# BlocoMotor.net
KiCad netlist of a schematic drawn in Altium Designer
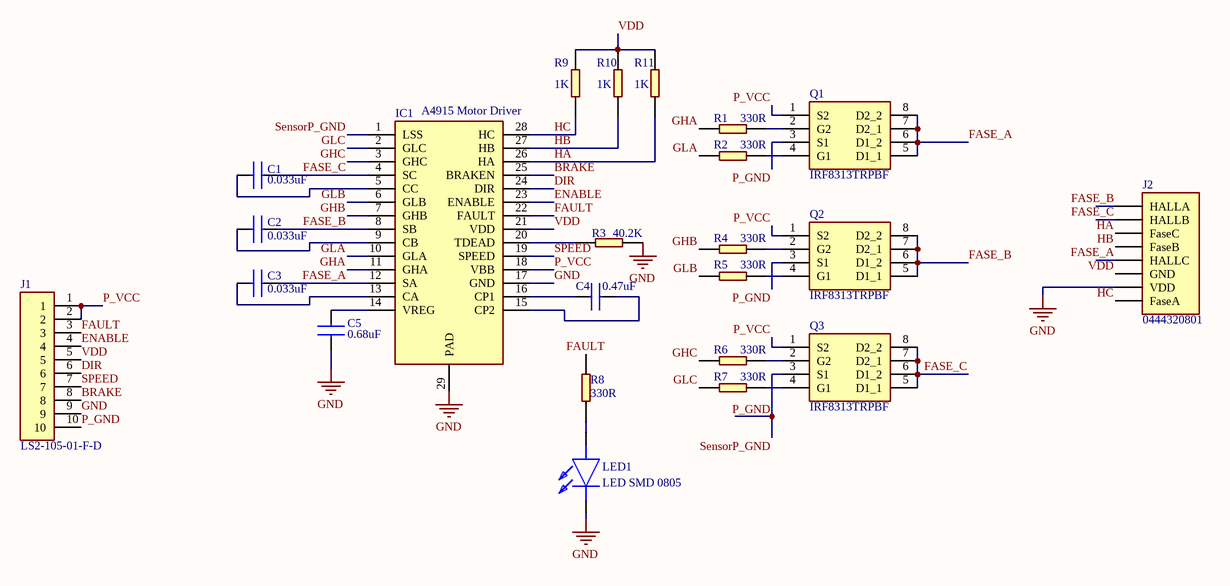
[diagram p0: BlocoMotor.SchDoc]

(export (version "E")
  (design (tool "Eeschema 10.0.6"))
  (components
    (comp (ref "C1")
      (value "0.033uF")
      (footprint "LIB_PCB_Kick:CAP0805 50v")
      (description "Capacitor\r\n08055A101JAT2A")
      (fields
        (field (name "MANUFACTURER_PART_NUMBER") "08055A101JAT2A")
        (field (name "MOUSER PART NUMBER") "581-08055A101J")
      )
      (libsource (lib "LIB_SCH_Main") (part "CAP 0805 50V"))
    )
    (comp (ref "C2")
      (value "0.033uF")
      (footprint "LIB_PCB_Kick:CAP0805 50v")
      (description "Capacitor\r\n08055A101JAT2A")
      (fields
        (field (name "MANUFACTURER_PART_NUMBER") "08055A101JAT2A")
        (field (name "MOUSER PART NUMBER") "581-08055A101J")
      )
      (libsource (lib "LIB_SCH_Main") (part "CAP 0805 50V"))
    )
    (comp (ref "C3")
      (value "0.033uF")
      (footprint "LIB_PCB_Kick:CAP0805 50v")
      (description "Capacitor\r\n08055A101JAT2A")
      (fields
        (field (name "MANUFACTURER_PART_NUMBER") "08055A101JAT2A")
        (field (name "MOUSER PART NUMBER") "581-08055A101J")
      )
      (libsource (lib "LIB_SCH_Main") (part "CAP 0805 50V"))
    )
    (comp (ref "C4")
      (value "0.47uF")
      (footprint "LIB_PCB_Kick:CAP0805 50v")
      (description "Capacitor\r\n08055A101JAT2A")
      (fields
        (field (name "MANUFACTURER_PART_NUMBER") "08055A101JAT2A")
        (field (name "MOUSER PART NUMBER") "581-08055A101J")
      )
      (libsource (lib "LIB_SCH_Main") (part "CAP 0805 50V"))
    )
    (comp (ref "C5")
      (value "0.68uF")
      (footprint "LIB_PCB_Kick:CAP0805 50v")
      (description "Capacitor\r\n08055A101JAT2A")
      (fields
        (field (name "MANUFACTURER_PART_NUMBER") "08055A101JAT2A")
        (field (name "MOUSER PART NUMBER") "581-08055A101J")
      )
      (libsource (lib "LIB_SCH_Main") (part "CAP 0805 50V"))
    )
    (comp (ref "IC1")
      (value "A4915 Motor Driver")
      (footprint "LIB_PCB_MAIN:A4915 Motor Driver")
      (fields (field (name "MANUFACTURER_PART_NUMBER") "A4915MLPTR-T"))
      (libsource (lib "LIB_SCH_MAIN") (part "A4915 Motor Driver"))
    )
    (comp (ref "J1")
      (value "LS2-105-01-F-D")
      (footprint "LIB_PCB_MAIN:CONN SINAL 10POS")
      (description "CONN SELF-MATE 10POS VERT GOLD\r\n\r\nSAM11451-ND\r\n\r\nLS2-105-01-F-D")
      (fields
        (field (name "MANUFACTURER_PART_NUMBER") "10132797-015100LF")
        (field (name "MOUSER PART NUMBER") "649-10132797015100LF")
      )
      (libsource (lib "LIB_SCH_MAIN") (part "CONN SInal Motor"))
    )
    (comp (ref "J2")
      (value "0444320801")
      (footprint "LIB_PCB_MAIN:CONN Main Motor")
      (fields (field (name "MANUFACTURER_PART_NUMBER") "0444320802"))
      (libsource (lib "LIB_SCH_Main") (part "CONN Main Motor"))
    )
    (comp (ref "LED1")
      (value "LED SMD 0805")
      (footprint "LIB_PCB_MAIN:LED SMD")
      (fields
        (field (name "MANUFACTURER_PART_NUMBER") "LTST-C170KRKT")
        (field (name "MOUSER PART NUMBER") "859-LTST-C170KRKT")
        (field (name "RS PART NUMBER") "6920916P")
      )
      (libsource (lib "LIB_SCH_MAIN") (part "LED SMD 0805"))
    )
    (comp (ref "Q1")
      (value "IRF8313TRPBF")
      (footprint "LIB_PCB_MAIN:MOSFET MOTOR 2N-CH 30V 9.7A 8-SOIC")
      (description "Mosfet Array 2 N-Channel (Dual) 30V 9.7A 2W Surface Mount 8-SO\r\n\r\nIRF8313TRPBFTR-ND")
      (fields
        (field (name "MOUSER PART NUMBER") "942-IRF8313TRPBF")
        (field (name "RS PART NUMBER") "8273903")
      )
      (libsource (lib "LIB_SCH_MAIN") (part "MOSFET MOTOR 2N-CH 30V 9.7A 8-SOIC"))
    )
    (comp (ref "Q2")
      (value "IRF8313TRPBF")
      (footprint "LIB_PCB_MAIN:MOSFET MOTOR 2N-CH 30V 9.7A 8-SOIC")
      (description "Mosfet Array 2 N-Channel (Dual) 30V 9.7A 2W Surface Mount 8-SO\r\n\r\nIRF8313TRPBFTR-ND")
      (fields
        (field (name "MOUSER PART NUMBER") "942-IRF8313TRPBF")
        (field (name "RS PART NUMBER") "8273903")
      )
      (libsource (lib "LIB_SCH_MAIN") (part "MOSFET MOTOR 2N-CH 30V 9.7A 8-SOIC"))
    )
    (comp (ref "Q3")
      (value "IRF8313TRPBF")
      (footprint "LIB_PCB_MAIN:MOSFET MOTOR 2N-CH 30V 9.7A 8-SOIC")
      (description "Mosfet Array 2 N-Channel (Dual) 30V 9.7A 2W Surface Mount 8-SO\r\n\r\nIRF8313TRPBFTR-ND")
      (fields
        (field (name "MOUSER PART NUMBER") "942-IRF8313TRPBF")
        (field (name "RS PART NUMBER") "8273903")
      )
      (libsource (lib "LIB_SCH_MAIN") (part "MOSFET MOTOR 2N-CH 30V 9.7A 8-SOIC"))
    )
    (comp (ref "R1")
      (value "330R")
      (footprint "LIB_PCB_Kick:RES 0805")
      (description "Resistor")
      (fields
        (field (name "MANUFACTURER_PART_NUMBER") "CPF0805B105RE1")
        (field (name "MOUSER PART NUMBER") "279-CPF0805B105RE1")
      )
      (libsource (lib "") (part "Resistor 0805_1"))
    )
    (comp (ref "R2")
      (value "330R")
      (footprint "LIB_PCB_Kick:RES 0805")
      (description "Resistor")
      (fields
        (field (name "MANUFACTURER_PART_NUMBER") "CPF0805B105RE1")
        (field (name "MOUSER PART NUMBER") "279-CPF0805B105RE1")
      )
      (libsource (lib "") (part "Resistor 0805_1"))
    )
    (comp (ref "R3")
      (value "40.2K")
      (footprint "LIB_PCB_Kick:RES 0805")
      (description "Resistor")
      (fields
        (field (name "MANUFACTURER_PART_NUMBER") "CPF0805B105RE1")
        (field (name "MOUSER PART NUMBER") "279-CPF0805B105RE1")
      )
      (libsource (lib "") (part "Resistor 0805_1"))
    )
    (comp (ref "R4")
      (value "330R")
      (footprint "LIB_PCB_Kick:RES 0805")
      (description "Resistor")
      (fields
        (field (name "MANUFACTURER_PART_NUMBER") "CPF0805B105RE1")
        (field (name "MOUSER PART NUMBER") "279-CPF0805B105RE1")
      )
      (libsource (lib "") (part "Resistor 0805_1"))
    )
    (comp (ref "R5")
      (value "330R")
      (footprint "LIB_PCB_Kick:RES 0805")
      (description "Resistor")
      (fields
        (field (name "MANUFACTURER_PART_NUMBER") "CPF0805B105RE1")
        (field (name "MOUSER PART NUMBER") "279-CPF0805B105RE1")
      )
      (libsource (lib "") (part "Resistor 0805_1"))
    )
    (comp (ref "R6")
      (value "330R")
      (footprint "LIB_PCB_Kick:RES 0805")
      (description "Resistor")
      (fields
        (field (name "MANUFACTURER_PART_NUMBER") "CPF0805B105RE1")
        (field (name "MOUSER PART NUMBER") "279-CPF0805B105RE1")
      )
      (libsource (lib "") (part "Resistor 0805_1"))
    )
    (comp (ref "R7")
      (value "330R")
      (footprint "LIB_PCB_Kick:RES 0805")
      (description "Resistor")
      (fields
        (field (name "MANUFACTURER_PART_NUMBER") "CPF0805B105RE1")
        (field (name "MOUSER PART NUMBER") "279-CPF0805B105RE1")
      )
      (libsource (lib "") (part "Resistor 0805_1"))
    )
    (comp (ref "R8")
      (value "330R")
      (footprint "LIB_PCB_Kick:RES 0805")
      (description "Resistor")
      (fields
        (field (name "MANUFACTURER_PART_NUMBER") "CPF0805B105RE1")
        (field (name "MOUSER PART NUMBER") "279-CPF0805B105RE1")
      )
      (libsource (lib "LIB_SCH_Main") (part "Resistor 0805"))
    )
    (comp (ref "R9")
      (value "1K")
      (footprint "LIB_PCB_Kick:RES 0805")
      (description "Resistor")
      (fields
        (field (name "MANUFACTURER_PART_NUMBER") "CPF0805B105RE1")
        (field (name "MOUSER PART NUMBER") "279-CPF0805B105RE1")
      )
      (libsource (lib "LIB_SCH_Main") (part "Resistor 0805"))
    )
    (comp (ref "R10")
      (value "1K")
      (footprint "LIB_PCB_Kick:RES 0805")
      (description "Resistor")
      (fields
        (field (name "MANUFACTURER_PART_NUMBER") "CPF0805B105RE1")
        (field (name "MOUSER PART NUMBER") "279-CPF0805B105RE1")
      )
      (libsource (lib "LIB_SCH_Main") (part "Resistor 0805"))
    )
    (comp (ref "R11")
      (value "1K")
      (footprint "LIB_PCB_Kick:RES 0805")
      (description "Resistor")
      (fields
        (field (name "MANUFACTURER_PART_NUMBER") "CPF0805B105RE1")
        (field (name "MOUSER PART NUMBER") "279-CPF0805B105RE1")
      )
      (libsource (lib "LIB_SCH_Main") (part "Resistor 0805"))
    )
  )
  (nets
    (net (code "1") (name "/BRAKE") (class "Default")
      (node (ref "IC1") (pin "25") (pinfunction "BRAKEN_25") (pintype "passive"))
      (node (ref "J1") (pin "8") (pinfunction "8_8") (pintype "passive"))
    )
    (net (code "2") (name "/DIR") (class "Default")
      (node (ref "IC1") (pin "24") (pinfunction "DIR_24") (pintype "passive"))
      (node (ref "J1") (pin "6") (pinfunction "6_6") (pintype "passive"))
    )
    (net (code "3") (name "/ENABLE") (class "Default")
      (node (ref "IC1") (pin "23") (pinfunction "ENABLE_23") (pintype "passive"))
      (node (ref "J1") (pin "4") (pinfunction "4_4") (pintype "passive"))
    )
    (net (code "4") (name "/FASE_A") (class "Default")
      (node (ref "C3") (pin "1") (pinfunction "1_1") (pintype "passive"))
      (node (ref "IC1") (pin "12") (pinfunction "SA_12") (pintype "passive"))
      (node (ref "J2") (pin "5") (pinfunction "HALLC_5") (pintype "passive"))
      (node (ref "Q1") (pin "5") (pinfunction "D1_1_5") (pintype "passive"))
      (node (ref "Q1") (pin "6") (pinfunction "D1_2_6") (pintype "passive"))
      (node (ref "Q1") (pin "7") (pinfunction "D2_1_7") (pintype "passive"))
      (node (ref "Q1") (pin "8") (pinfunction "D2_2_8") (pintype "passive"))
    )
    (net (code "5") (name "/FASE_B") (class "Default")
      (node (ref "C2") (pin "1") (pinfunction "1_1") (pintype "passive"))
      (node (ref "IC1") (pin "8") (pinfunction "SB_8") (pintype "passive"))
      (node (ref "J2") (pin "1") (pinfunction "HALLA_1") (pintype "passive"))
      (node (ref "Q2") (pin "5") (pinfunction "D1_1_5") (pintype "passive"))
      (node (ref "Q2") (pin "6") (pinfunction "D1_2_6") (pintype "passive"))
      (node (ref "Q2") (pin "7") (pinfunction "D2_1_7") (pintype "passive"))
      (node (ref "Q2") (pin "8") (pinfunction "D2_2_8") (pintype "passive"))
    )
    (net (code "6") (name "/FASE_C") (class "Default")
      (node (ref "C1") (pin "1") (pinfunction "1_1") (pintype "passive"))
      (node (ref "IC1") (pin "4") (pinfunction "SC_4") (pintype "passive"))
      (node (ref "J2") (pin "2") (pinfunction "HALLB_2") (pintype "passive"))
      (node (ref "Q3") (pin "5") (pinfunction "D1_1_5") (pintype "passive"))
      (node (ref "Q3") (pin "6") (pinfunction "D1_2_6") (pintype "passive"))
      (node (ref "Q3") (pin "7") (pinfunction "D2_1_7") (pintype "passive"))
      (node (ref "Q3") (pin "8") (pinfunction "D2_2_8") (pintype "passive"))
    )
    (net (code "7") (name "/FAULT") (class "Default")
      (node (ref "IC1") (pin "22") (pinfunction "FAULT_22") (pintype "passive"))
      (node (ref "J1") (pin "3") (pinfunction "3_3") (pintype "passive"))
      (node (ref "R8") (pin "1") (pinfunction "1_1") (pintype "passive"))
    )
    (net (code "8") (name "/GHA") (class "Default")
      (node (ref "IC1") (pin "11") (pinfunction "GHA_11") (pintype "passive"))
      (node (ref "R1") (pin "1") (pinfunction "1_1") (pintype "passive"))
    )
    (net (code "9") (name "/GHB") (class "Default")
      (node (ref "IC1") (pin "7") (pinfunction "GHB_7") (pintype "passive"))
      (node (ref "R4") (pin "1") (pinfunction "1_1") (pintype "passive"))
    )
    (net (code "10") (name "/GHC") (class "Default")
      (node (ref "IC1") (pin "3") (pinfunction "GHC_3") (pintype "passive"))
      (node (ref "R6") (pin "1") (pinfunction "1_1") (pintype "passive"))
    )
    (net (code "11") (name "/GLA") (class "Default")
      (node (ref "IC1") (pin "10") (pinfunction "GLA_10") (pintype "passive"))
      (node (ref "R2") (pin "1") (pinfunction "1_1") (pintype "passive"))
    )
    (net (code "12") (name "/GLB") (class "Default")
      (node (ref "IC1") (pin "6") (pinfunction "GLB_6") (pintype "passive"))
      (node (ref "R5") (pin "1") (pinfunction "1_1") (pintype "passive"))
    )
    (net (code "13") (name "/GLC") (class "Default")
      (node (ref "IC1") (pin "2") (pinfunction "GLC_2") (pintype "passive"))
      (node (ref "R7") (pin "1") (pinfunction "1_1") (pintype "passive"))
    )
    (net (code "14") (name "/HA") (class "Default")
      (node (ref "IC1") (pin "26") (pinfunction "HA_26") (pintype "passive"))
      (node (ref "J2") (pin "3") (pinfunction "FaseC_3") (pintype "passive"))
      (node (ref "R11") (pin "2") (pinfunction "2_2") (pintype "passive"))
    )
    (net (code "15") (name "/HB") (class "Default")
      (node (ref "IC1") (pin "27") (pinfunction "HB_27") (pintype "passive"))
      (node (ref "J2") (pin "4") (pinfunction "FaseB_4") (pintype "passive"))
      (node (ref "R10") (pin "2") (pinfunction "2_2") (pintype "passive"))
    )
    (net (code "16") (name "/HC") (class "Default")
      (node (ref "IC1") (pin "28") (pinfunction "HC_28") (pintype "passive"))
      (node (ref "J2") (pin "8") (pinfunction "FaseA_8") (pintype "passive"))
      (node (ref "R9") (pin "2") (pinfunction "2_2") (pintype "passive"))
    )
    (net (code "17") (name "/P_GND") (class "Default")
      (node (ref "IC1") (pin "1") (pinfunction "LSS_1") (pintype "passive"))
      (node (ref "J1") (pin "10") (pinfunction "10_10") (pintype "passive"))
      (node (ref "Q1") (pin "3") (pinfunction "S1_3") (pintype "passive"))
      (node (ref "Q2") (pin "3") (pinfunction "S1_3") (pintype "passive"))
      (node (ref "Q3") (pin "3") (pinfunction "S1_3") (pintype "passive"))
    )
    (net (code "18") (name "/P_VCC") (class "Default")
      (node (ref "IC1") (pin "18") (pinfunction "VBB_18") (pintype "passive"))
      (node (ref "J1") (pin "1") (pinfunction "1_1") (pintype "passive"))
      (node (ref "J1") (pin "2") (pinfunction "2_2") (pintype "passive"))
      (node (ref "Q1") (pin "1") (pinfunction "S2_1") (pintype "passive"))
      (node (ref "Q2") (pin "1") (pinfunction "S2_1") (pintype "passive"))
      (node (ref "Q3") (pin "1") (pinfunction "S2_1") (pintype "passive"))
    )
    (net (code "19") (name "/SPEED") (class "Default")
      (node (ref "IC1") (pin "19") (pinfunction "SPEED_19") (pintype "passive"))
      (node (ref "J1") (pin "7") (pinfunction "7_7") (pintype "passive"))
    )
    (net (code "20") (name "/VDD") (class "Default")
      (node (ref "IC1") (pin "21") (pinfunction "VDD_21") (pintype "passive"))
      (node (ref "J1") (pin "5") (pinfunction "5_5") (pintype "passive"))
      (node (ref "J2") (pin "6") (pinfunction "GND_6") (pintype "passive"))
      (node (ref "R10") (pin "1") (pinfunction "1_1") (pintype "passive"))
      (node (ref "R11") (pin "1") (pinfunction "1_1") (pintype "passive"))
      (node (ref "R9") (pin "1") (pinfunction "1_1") (pintype "passive"))
    )
    (net (code "21") (name "GND") (class "Default")
      (node (ref "C5") (pin "1") (pinfunction "1_1") (pintype "passive"))
      (node (ref "IC1") (pin "17") (pinfunction "GND_17") (pintype "passive"))
      (node (ref "IC1") (pin "29") (pinfunction "PAD_29") (pintype "passive"))
      (node (ref "J1") (pin "9") (pinfunction "9_9") (pintype "passive"))
      (node (ref "J2") (pin "7") (pinfunction "VDD_7") (pintype "passive"))
      (node (ref "LED1") (pin "1") (pinfunction "K_1") (pintype "passive"))
      (node (ref "R3") (pin "2") (pinfunction "2_2") (pintype "passive"))
    )
    (net (code "22") (name "Net-(IC1-CA)") (class "Default")
      (node (ref "C3") (pin "2") (pinfunction "2_2") (pintype "passive"))
      (node (ref "IC1") (pin "13") (pinfunction "CA_13") (pintype "passive"))
    )
    (net (code "23") (name "Net-(IC1-CB)") (class "Default")
      (node (ref "C2") (pin "2") (pinfunction "2_2") (pintype "passive"))
      (node (ref "IC1") (pin "9") (pinfunction "CB_9") (pintype "passive"))
    )
    (net (code "24") (name "Net-(IC1-CC)") (class "Default")
      (node (ref "C1") (pin "2") (pinfunction "2_2") (pintype "passive"))
      (node (ref "IC1") (pin "5") (pinfunction "CC_5") (pintype "passive"))
    )
    (net (code "25") (name "Net-(IC1-CP1)") (class "Default")
      (node (ref "C4") (pin "2") (pinfunction "2_2") (pintype "passive"))
      (node (ref "IC1") (pin "16") (pinfunction "CP1_16") (pintype "passive"))
    )
    (net (code "26") (name "Net-(IC1-CP2)") (class "Default")
      (node (ref "C4") (pin "1") (pinfunction "1_1") (pintype "passive"))
      (node (ref "IC1") (pin "15") (pinfunction "CP2_15") (pintype "passive"))
    )
    (net (code "27") (name "Net-(IC1-TDEAD)") (class "Default")
      (node (ref "IC1") (pin "20") (pinfunction "TDEAD_20") (pintype "passive"))
      (node (ref "R3") (pin "1") (pinfunction "1_1") (pintype "passive"))
    )
    (net (code "28") (name "Net-(IC1-VREG)") (class "Default")
      (node (ref "C5") (pin "2") (pinfunction "2_2") (pintype "passive"))
      (node (ref "IC1") (pin "14") (pinfunction "VREG_14") (pintype "passive"))
    )
    (net (code "29") (name "Net-(LED1-A)") (class "Default")
      (node (ref "LED1") (pin "2") (pinfunction "A_2") (pintype "passive"))
      (node (ref "R8") (pin "2") (pinfunction "2_2") (pintype "passive"))
    )
    (net (code "30") (name "Net-(Q1-G1)") (class "Default")
      (node (ref "Q1") (pin "4") (pinfunction "G1_4") (pintype "passive"))
      (node (ref "R2") (pin "2") (pinfunction "2_2") (pintype "passive"))
    )
    (net (code "31") (name "Net-(Q1-G2)") (class "Default")
      (node (ref "Q1") (pin "2") (pinfunction "G2_2") (pintype "passive"))
      (node (ref "R1") (pin "2") (pinfunction "2_2") (pintype "passive"))
    )
    (net (code "32") (name "Net-(Q2-G1)") (class "Default")
      (node (ref "Q2") (pin "4") (pinfunction "G1_4") (pintype "passive"))
      (node (ref "R5") (pin "2") (pinfunction "2_2") (pintype "passive"))
    )
    (net (code "33") (name "Net-(Q2-G2)") (class "Default")
      (node (ref "Q2") (pin "2") (pinfunction "G2_2") (pintype "passive"))
      (node (ref "R4") (pin "2") (pinfunction "2_2") (pintype "passive"))
    )
    (net (code "34") (name "Net-(Q3-G1)") (class "Default")
      (node (ref "Q3") (pin "4") (pinfunction "G1_4") (pintype "passive"))
      (node (ref "R7") (pin "2") (pinfunction "2_2") (pintype "passive"))
    )
    (net (code "35") (name "Net-(Q3-G2)") (class "Default")
      (node (ref "Q3") (pin "2") (pinfunction "G2_2") (pintype "passive"))
      (node (ref "R6") (pin "2") (pinfunction "2_2") (pintype "passive"))
    )
  )
)
